# CAMERA.net
KiCad netlist of a schematic drawn in Altium Designer
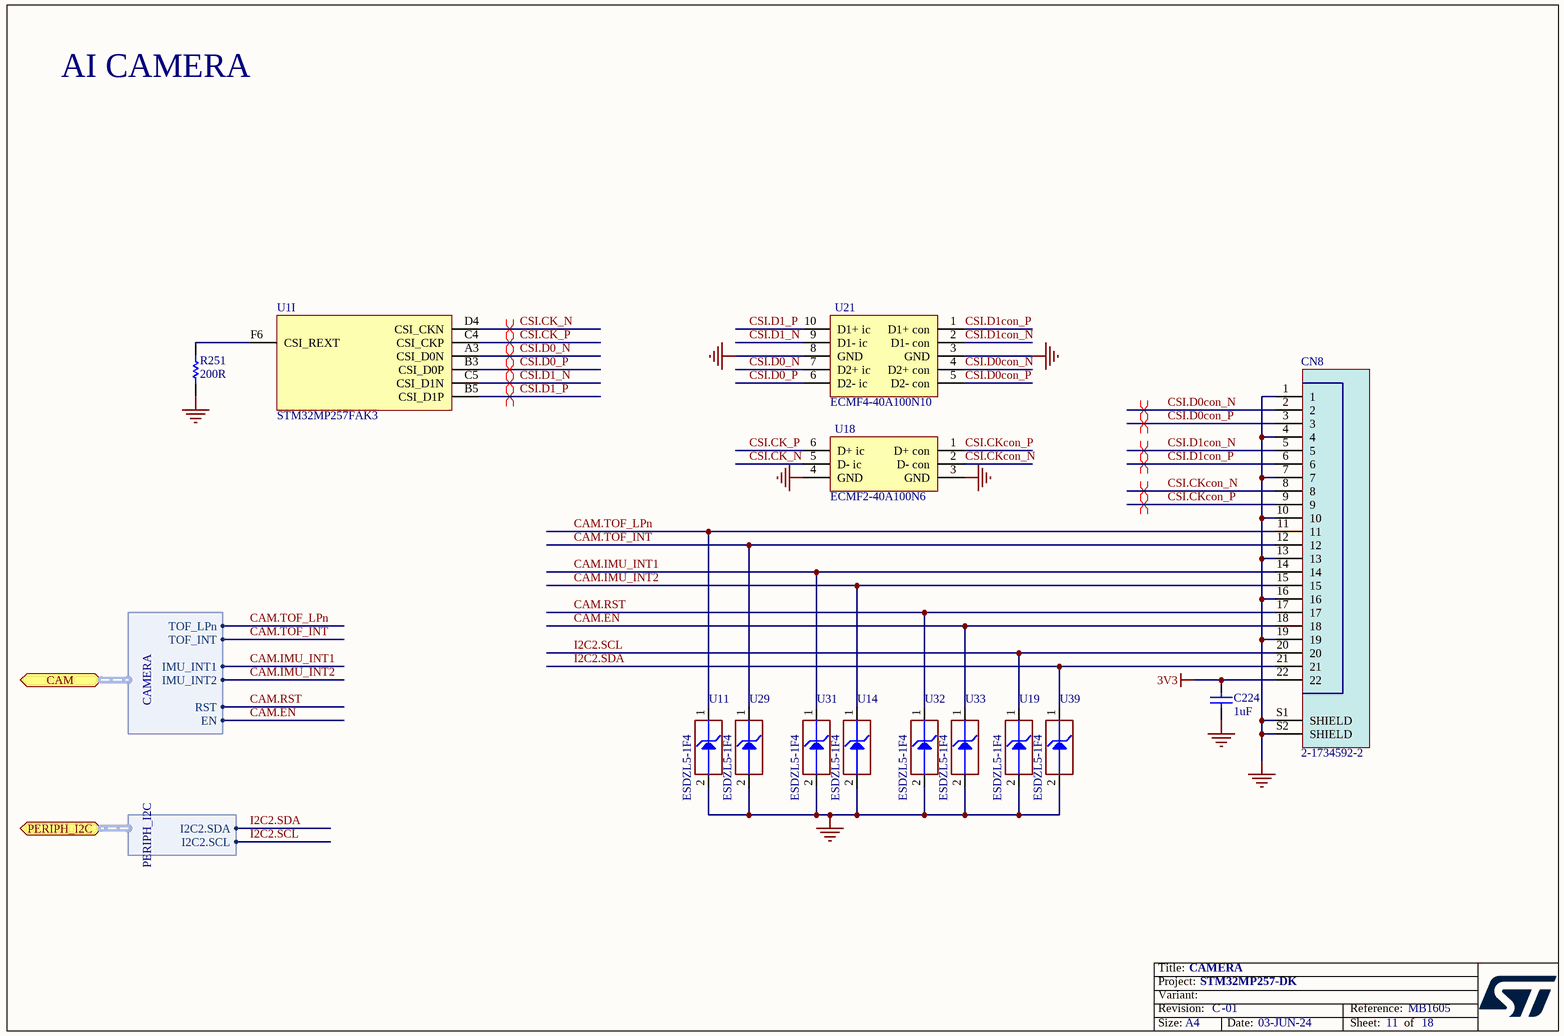
[diagram p0: CAMERA.SchDoc]

(export (version "E")
  (design (tool "Eeschema 10.0.6"))
  (components
    (comp (ref "C224")
      (value "1uF")
      (footprint "C0402")
      (description "Capacitor, MLCC, 1uF, 25V, X5R, +/-10%, 0402, T=0,5mm")
      (fields
        (field (name "INTERNAL_PART_NUMBER") "MCD-00095")
        (field (name "MANUFACTURER_PART_NUMBER") "GRM155R61E105KA12")
      )
      (libsource (lib "MCD_PARTS_database") (part "Capacitor"))
    )
    (comp (ref "CN8")
      (value "2-1734592-2")
      (footprint "CON_TE-CONNECTIVITY_2-1734592-2_INV")
      (description "Socket_FFC/FPC, 22pins, 0.5mm, RA, SMD, T=2mm")
      (fields
        (field (name "INTERNAL_PART_NUMBER") "MCD-03600")
        (field (name "MANUFACTURER") "TE CONNECTIVITY")
      )
      (libsource (lib "MCD_PARTS_database") (part "2-1734592-2"))
    )
    (comp (ref "R251")
      (value "200R")
      (footprint "R0402")
      (description "Resistor, 200R, 0402, +/-1%, 1/16W")
      (fields
        (field (name "INTERNAL_PART_NUMBER") "MCD-00417")
        (field (name "MANUFACTURER_PART_NUMBER") "RC0402FR-07200RL")
      )
      (libsource (lib "MCD_PARTS_database") (part "Resistor"))
    )
    (comp (ref "U1")
      (value "STM32MP257FAK3")
      (footprint "ICC_TFBGA424_14X14_P050_H1P20_CODE-B0A2")
      (description "MPU , 2xCortex-A35@1.5GHz, Cortex-M33@400MHz, TFBGA 14x14, pitch 0.5, 648KB SRAM, With Crypto")
      (fields
        (field (name "INTERNAL_PART_NUMBER") "MCD-03375")
        (field (name "MANUFACTURER") "STMICROELECTRONICS")
      )
      (libsource (lib "MCD_PARTS_database") (part "STM32MP257FAK3"))
    )
    (comp (ref "U11")
      (value "ESDZL5-1F4")
      (footprint "ESD_ST0201")
      (description "ESD protection , 0201")
      (fields
        (field (name "INTERNAL_PART_NUMBER") "MCD-03501")
        (field (name "MANUFACTURER") "STMICROELECTRONICS")
      )
      (libsource (lib "MCD_PARTS_database") (part "ESD-TRANSIL"))
    )
    (comp (ref "U14")
      (value "ESDZL5-1F4")
      (footprint "ESD_ST0201")
      (description "ESD protection , 0201")
      (fields
        (field (name "INTERNAL_PART_NUMBER") "MCD-03501")
        (field (name "MANUFACTURER") "STMICROELECTRONICS")
      )
      (libsource (lib "MCD_PARTS_database") (part "ESD-TRANSIL"))
    )
    (comp (ref "U18")
      (value "ECMF2-40A100N6")
      (footprint "ESD_UQFN-6L_1P45X1P4_P040")
      (description "ESD protection & Common Filter High Speed serial Interfaces , 0.4 pitch")
      (fields
        (field (name "INTERNAL_PART_NUMBER") "MCD-03060")
        (field (name "MANUFACTURER") "STMICROELECTRONICS")
      )
      (libsource (lib "MCD_PARTS_database") (part "ECMF2-40A100N6"))
    )
    (comp (ref "U19")
      (value "ESDZL5-1F4")
      (footprint "ESD_ST0201")
      (description "ESD protection , 0201")
      (fields
        (field (name "INTERNAL_PART_NUMBER") "MCD-03501")
        (field (name "MANUFACTURER") "STMICROELECTRONICS")
      )
      (libsource (lib "MCD_PARTS_database") (part "ESD-TRANSIL"))
    )
    (comp (ref "U21")
      (value "ECMF4-40A100N10")
      (footprint "ESD_UQFN-10L_2P25X1P4_P040")
      (description "ESD protection & Common Filter High Speed serial Interfaces , 0.4 pitch")
      (fields
        (field (name "INTERNAL_PART_NUMBER") "MCD-03059")
        (field (name "MANUFACTURER") "STMICROELECTRONICS")
      )
      (libsource (lib "MCD_PARTS_database") (part "ECMF4-40A100N10"))
    )
    (comp (ref "U29")
      (value "ESDZL5-1F4")
      (footprint "ESD_ST0201")
      (description "ESD protection , 0201")
      (fields
        (field (name "INTERNAL_PART_NUMBER") "MCD-03501")
        (field (name "MANUFACTURER") "STMICROELECTRONICS")
      )
      (libsource (lib "MCD_PARTS_database") (part "ESD-TRANSIL"))
    )
    (comp (ref "U31")
      (value "ESDZL5-1F4")
      (footprint "ESD_ST0201")
      (description "ESD protection , 0201")
      (fields
        (field (name "INTERNAL_PART_NUMBER") "MCD-03501")
        (field (name "MANUFACTURER") "STMICROELECTRONICS")
      )
      (libsource (lib "MCD_PARTS_database") (part "ESD-TRANSIL"))
    )
    (comp (ref "U32")
      (value "ESDZL5-1F4")
      (footprint "ESD_ST0201")
      (description "ESD protection , 0201")
      (fields
        (field (name "INTERNAL_PART_NUMBER") "MCD-03501")
        (field (name "MANUFACTURER") "STMICROELECTRONICS")
      )
      (libsource (lib "MCD_PARTS_database") (part "ESD-TRANSIL"))
    )
    (comp (ref "U33")
      (value "ESDZL5-1F4")
      (footprint "ESD_ST0201")
      (description "ESD protection , 0201")
      (fields
        (field (name "INTERNAL_PART_NUMBER") "MCD-03501")
        (field (name "MANUFACTURER") "STMICROELECTRONICS")
      )
      (libsource (lib "MCD_PARTS_database") (part "ESD-TRANSIL"))
    )
    (comp (ref "U39")
      (value "ESDZL5-1F4")
      (footprint "ESD_ST0201")
      (description "ESD protection , 0201")
      (fields
        (field (name "INTERNAL_PART_NUMBER") "MCD-03501")
        (field (name "MANUFACTURER") "STMICROELECTRONICS")
      )
      (libsource (lib "MCD_PARTS_database") (part "ESD-TRANSIL"))
    )
  )
  (nets
    (net (code "3") (name "/CAM.EN") (class "Default")
      (node (ref "CN8") (pin "18") (pinfunction "18_18") (pintype "passive"))
      (node (ref "U33") (pin "1") (pinfunction "IO1_1") (pintype "passive"))
    )
    (net (code "4") (name "/CAM.IMU_INT1") (class "Default")
      (node (ref "CN8") (pin "14") (pinfunction "14_14") (pintype "passive"))
      (node (ref "U31") (pin "1") (pinfunction "IO1_1") (pintype "passive"))
    )
    (net (code "5") (name "/CAM.IMU_INT2") (class "Default")
      (node (ref "CN8") (pin "15") (pinfunction "15_15") (pintype "passive"))
      (node (ref "U14") (pin "1") (pinfunction "IO1_1") (pintype "passive"))
    )
    (net (code "6") (name "/CAM.RST") (class "Default")
      (node (ref "CN8") (pin "17") (pinfunction "17_17") (pintype "passive"))
      (node (ref "U32") (pin "1") (pinfunction "IO1_1") (pintype "passive"))
    )
    (net (code "7") (name "/CAM.TOF_INT") (class "Default")
      (node (ref "CN8") (pin "12") (pinfunction "12_12") (pintype "passive"))
      (node (ref "U29") (pin "1") (pinfunction "IO1_1") (pintype "passive"))
    )
    (net (code "8") (name "/CAM.TOF_LPn") (class "Default")
      (node (ref "CN8") (pin "11") (pinfunction "11_11") (pintype "passive"))
      (node (ref "U11") (pin "1") (pinfunction "IO1_1") (pintype "passive"))
    )
    (net (code "9") (name "/CSI.CK_N") (class "Default")
      (node (ref "U1") (pin "D4") (pinfunction "CSI_CKN_D4") (pintype "passive"))
      (node (ref "U18") (pin "5") (pinfunction "D-_ic_5") (pintype "passive"))
    )
    (net (code "10") (name "/CSI.CK_P") (class "Default")
      (node (ref "U1") (pin "C4") (pinfunction "CSI_CKP_C4") (pintype "passive"))
      (node (ref "U18") (pin "6") (pinfunction "D+_ic_6") (pintype "passive"))
    )
    (net (code "11") (name "/CSI.CKcon_N") (class "Default")
      (node (ref "CN8") (pin "8") (pinfunction "8_8") (pintype "passive"))
      (node (ref "U18") (pin "2") (pinfunction "D-_con_2") (pintype "passive"))
    )
    (net (code "12") (name "/CSI.CKcon_P") (class "Default")
      (node (ref "CN8") (pin "9") (pinfunction "9_9") (pintype "passive"))
      (node (ref "U18") (pin "1") (pinfunction "D+_con_1") (pintype "passive"))
    )
    (net (code "13") (name "/CSI.D0_N") (class "Default")
      (node (ref "U1") (pin "A3") (pinfunction "CSI_D0N_A3") (pintype "passive"))
      (node (ref "U21") (pin "7") (pinfunction "D2+_ic_7") (pintype "passive"))
    )
    (net (code "14") (name "/CSI.D0_P") (class "Default")
      (node (ref "U1") (pin "B3") (pinfunction "CSI_D0P_B3") (pintype "passive"))
      (node (ref "U21") (pin "6") (pinfunction "D2-_ic_6") (pintype "passive"))
    )
    (net (code "15") (name "/CSI.D0con_N") (class "Default")
      (node (ref "CN8") (pin "2") (pinfunction "2_2") (pintype "passive"))
      (node (ref "U21") (pin "4") (pinfunction "D2+_con_4") (pintype "passive"))
    )
    (net (code "16") (name "/CSI.D0con_P") (class "Default")
      (node (ref "CN8") (pin "3") (pinfunction "3_3") (pintype "passive"))
      (node (ref "U21") (pin "5") (pinfunction "D2-_con_5") (pintype "passive"))
    )
    (net (code "17") (name "/CSI.D1_N") (class "Default")
      (node (ref "U1") (pin "C5") (pinfunction "CSI_D1N_C5") (pintype "passive"))
      (node (ref "U21") (pin "9") (pinfunction "D1-_ic_9") (pintype "passive"))
    )
    (net (code "18") (name "/CSI.D1_P") (class "Default")
      (node (ref "U1") (pin "B5") (pinfunction "CSI_D1P_B5") (pintype "passive"))
      (node (ref "U21") (pin "10") (pinfunction "D1+_ic_10") (pintype "passive"))
    )
    (net (code "19") (name "/CSI.D1con_N") (class "Default")
      (node (ref "CN8") (pin "5") (pinfunction "5_5") (pintype "passive"))
      (node (ref "U21") (pin "2") (pinfunction "D1-_con_2") (pintype "passive"))
    )
    (net (code "20") (name "/CSI.D1con_P") (class "Default")
      (node (ref "CN8") (pin "6") (pinfunction "6_6") (pintype "passive"))
      (node (ref "U21") (pin "1") (pinfunction "D1+_con_1") (pintype "passive"))
    )
    (net (code "21") (name "/I2C2.SCL") (class "Default")
      (node (ref "CN8") (pin "20") (pinfunction "20_20") (pintype "passive"))
      (node (ref "U19") (pin "1") (pinfunction "IO1_1") (pintype "passive"))
    )
    (net (code "22") (name "/I2C2.SDA") (class "Default")
      (node (ref "CN8") (pin "21") (pinfunction "21_21") (pintype "passive"))
      (node (ref "U39") (pin "1") (pinfunction "IO1_1") (pintype "passive"))
    )
    (net (code "25") (name "3V3") (class "Default")
      (node (ref "C224") (pin "2") (pinfunction "2_2") (pintype "passive"))
      (node (ref "CN8") (pin "22") (pinfunction "22_22") (pintype "passive"))
    )
    (net (code "26") (name "GND") (class "Default")
      (node (ref "C224") (pin "1") (pinfunction "1_1") (pintype "passive"))
      (node (ref "CN8") (pin "1") (pinfunction "1_1") (pintype "passive"))
      (node (ref "CN8") (pin "10") (pinfunction "10_10") (pintype "passive"))
      (node (ref "CN8") (pin "13") (pinfunction "13_13") (pintype "passive"))
      (node (ref "CN8") (pin "16") (pinfunction "16_16") (pintype "passive"))
      (node (ref "CN8") (pin "19") (pinfunction "19_19") (pintype "passive"))
      (node (ref "CN8") (pin "4") (pinfunction "4_4") (pintype "passive"))
      (node (ref "CN8") (pin "7") (pinfunction "7_7") (pintype "passive"))
      (node (ref "CN8") (pin "S1") (pinfunction "SHIELD_S1") (pintype "passive"))
      (node (ref "CN8") (pin "S2") (pinfunction "SHIELD_S2") (pintype "passive"))
      (node (ref "R251") (pin "2") (pinfunction "2_2") (pintype "passive"))
      (node (ref "U11") (pin "2") (pinfunction "GND_2") (pintype "passive"))
      (node (ref "U14") (pin "2") (pinfunction "GND_2") (pintype "passive"))
      (node (ref "U18") (pin "3") (pinfunction "GND_3") (pintype "passive"))
      (node (ref "U18") (pin "4") (pinfunction "GND_4") (pintype "passive"))
      (node (ref "U19") (pin "2") (pinfunction "GND_2") (pintype "passive"))
      (node (ref "U21") (pin "3") (pinfunction "GND_3") (pintype "passive"))
      (node (ref "U21") (pin "8") (pinfunction "GND_8") (pintype "passive"))
      (node (ref "U29") (pin "2") (pinfunction "GND_2") (pintype "passive"))
      (node (ref "U31") (pin "2") (pinfunction "GND_2") (pintype "passive"))
      (node (ref "U32") (pin "2") (pinfunction "GND_2") (pintype "passive"))
      (node (ref "U33") (pin "2") (pinfunction "GND_2") (pintype "passive"))
      (node (ref "U39") (pin "2") (pinfunction "GND_2") (pintype "passive"))
    )
    (net (code "27") (name "Net-(U1I-CSI_REXT)") (class "Default")
      (node (ref "R251") (pin "1") (pinfunction "1_1") (pintype "passive"))
      (node (ref "U1") (pin "F6") (pinfunction "CSI_REXT_F6") (pintype "passive"))
    )
  )
)
